# batsch-env.net
KiCad netlist of a schematic drawn in Altium Designer
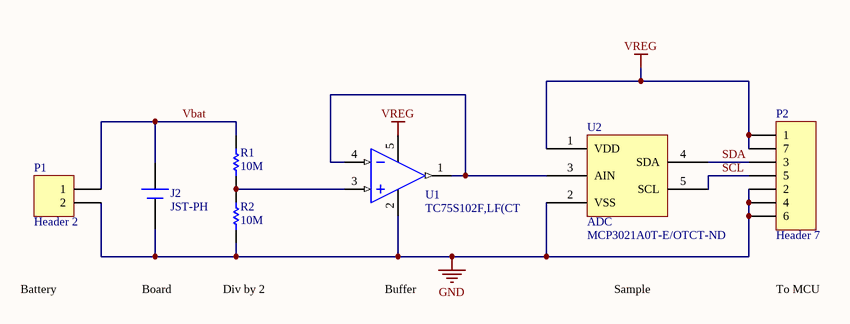
[diagram p0: batsch-env.SchDoc]

(export (version "E")
  (design (tool "Eeschema 10.0.6"))
  (components
    (comp (ref "J2")
      (value "JST-PH")
      (footprint "JST-PH")
      (description "Input/Output")
      (libsource (lib "EnviroMon") (part "JST-PH"))
    )
    (comp (ref "P1")
      (value "Header 2")
      (footprint "HDR1X2")
      (description "Header, 2-Pin")
      (fields (field (name "PUBLISHER") "Altium Limited"))
      (libsource (lib "Miscellaneous Connectors") (part "Header 2"))
    )
    (comp (ref "P2")
      (value "Header 7")
      (footprint "HDR1X7")
      (description "Header, 7-Pin")
      (fields (field (name "PUBLISHER") "Altium Limited"))
      (libsource (lib "EnviroMon") (part "Header 7"))
    )
    (comp (ref "R1")
      (value "10M")
      (footprint "1206")
      (description "Resistor")
      (fields
        (field (name "TOLERANCE") "10%")
        (field (name "Comment") "Res1")
        (field (name "PUBLISHER") "Altium Limited")
      )
      (libsource (lib "schlib-env") (part "resistor 10M"))
    )
    (comp (ref "R2")
      (value "10M")
      (footprint "1206")
      (description "Resistor")
      (fields
        (field (name "TOLERANCE") "10%")
        (field (name "Comment") "Res1")
        (field (name "PUBLISHER") "Altium Limited")
      )
      (libsource (lib "schlib-env") (part "resistor 10M"))
    )
    (comp (ref "U1")
      (value "TC75S102F,LF(CT")
      (footprint "OPAMP TOSHIBA")
      (description "Op Amp Single Ultra Low Current Amplifier 5.5V 5-Pin SMV T/R")
      (fields (field (name "MANUFACTURER") "Toshiba"))
      (libsource (lib "schlib-env") (part "TC75S102F,LF(CT"))
    )
    (comp (ref "U2")
      (value "ADC")
      (footprint "I2C SOT23")
      (description "1-Channel Single ADC SAR 22.3ksps 10-bit Serial Automotive 5-Pin SOT-23 T/R")
      (fields
        (field (name "MANUFACTURER") "Microchip")
        (field (name "MANUFACTURER PART NUMBER") "MCP3021A0T-E/OT")
        (field (name "SUPPLIER PART NUMBER 1") "MCP3021A0T-E/OTCT-ND")
      )
      (libsource (lib "schlib-env") (part "MCP3021A0T-E/OT"))
    )
  )
  (nets
    (net (code "1") (name "/SCL") (class "Default")
      (node (ref "P2") (pin "5") (pinfunction "5_5") (pintype "passive"))
      (node (ref "U2") (pin "5") (pinfunction "SCL_5") (pintype "passive"))
    )
    (net (code "2") (name "/SDA") (class "Default")
      (node (ref "P2") (pin "3") (pinfunction "3_3") (pintype "passive"))
      (node (ref "U2") (pin "4") (pinfunction "SDA_4") (pintype "passive"))
    )
    (net (code "3") (name "/Vbat") (class "Default")
      (node (ref "J2") (pin "1") (pinfunction "+_1") (pintype "passive"))
      (node (ref "P1") (pin "1") (pinfunction "1_1") (pintype "passive"))
      (node (ref "R1") (pin "1") (pinfunction "1_1") (pintype "passive"))
    )
    (net (code "4") (name "GND") (class "Default")
      (node (ref "J2") (pin "2") (pinfunction "-_2") (pintype "passive"))
      (node (ref "P1") (pin "2") (pinfunction "2_2") (pintype "passive"))
      (node (ref "P2") (pin "2") (pinfunction "2_2") (pintype "passive"))
      (node (ref "P2") (pin "4") (pinfunction "4_4") (pintype "passive"))
      (node (ref "P2") (pin "6") (pinfunction "6_6") (pintype "passive"))
      (node (ref "R2") (pin "2") (pinfunction "2_2") (pintype "passive"))
      (node (ref "U1") (pin "2") (pinfunction "Vss_2") (pintype "power_in"))
      (node (ref "U2") (pin "2") (pinfunction "VSS_2") (pintype "passive"))
    )
    (net (code "5") (name "Net-(U1-IN+)") (class "Default")
      (node (ref "R1") (pin "2") (pinfunction "2_2") (pintype "passive"))
      (node (ref "R2") (pin "1") (pinfunction "1_1") (pintype "passive"))
      (node (ref "U1") (pin "3") (pinfunction "IN+_3") (pintype "input"))
    )
    (net (code "6") (name "Net-(U1-IN-)") (class "Default")
      (node (ref "U1") (pin "1") (pinfunction "OUT_1") (pintype "output"))
      (node (ref "U1") (pin "4") (pinfunction "IN-_4") (pintype "input"))
      (node (ref "U2") (pin "3") (pinfunction "AIN_3") (pintype "passive"))
    )
    (net (code "7") (name "VREG") (class "Default")
      (node (ref "P2") (pin "1") (pinfunction "1_1") (pintype "passive"))
      (node (ref "P2") (pin "7") (pinfunction "7_7") (pintype "passive"))
      (node (ref "U1") (pin "5") (pinfunction "V+_5") (pintype "power_in"))
      (node (ref "U2") (pin "1") (pinfunction "VDD_1") (pintype "passive"))
    )
  )
)
